# RAM_EMMC_Power.net
KiCad netlist of a schematic drawn in Altium Designer
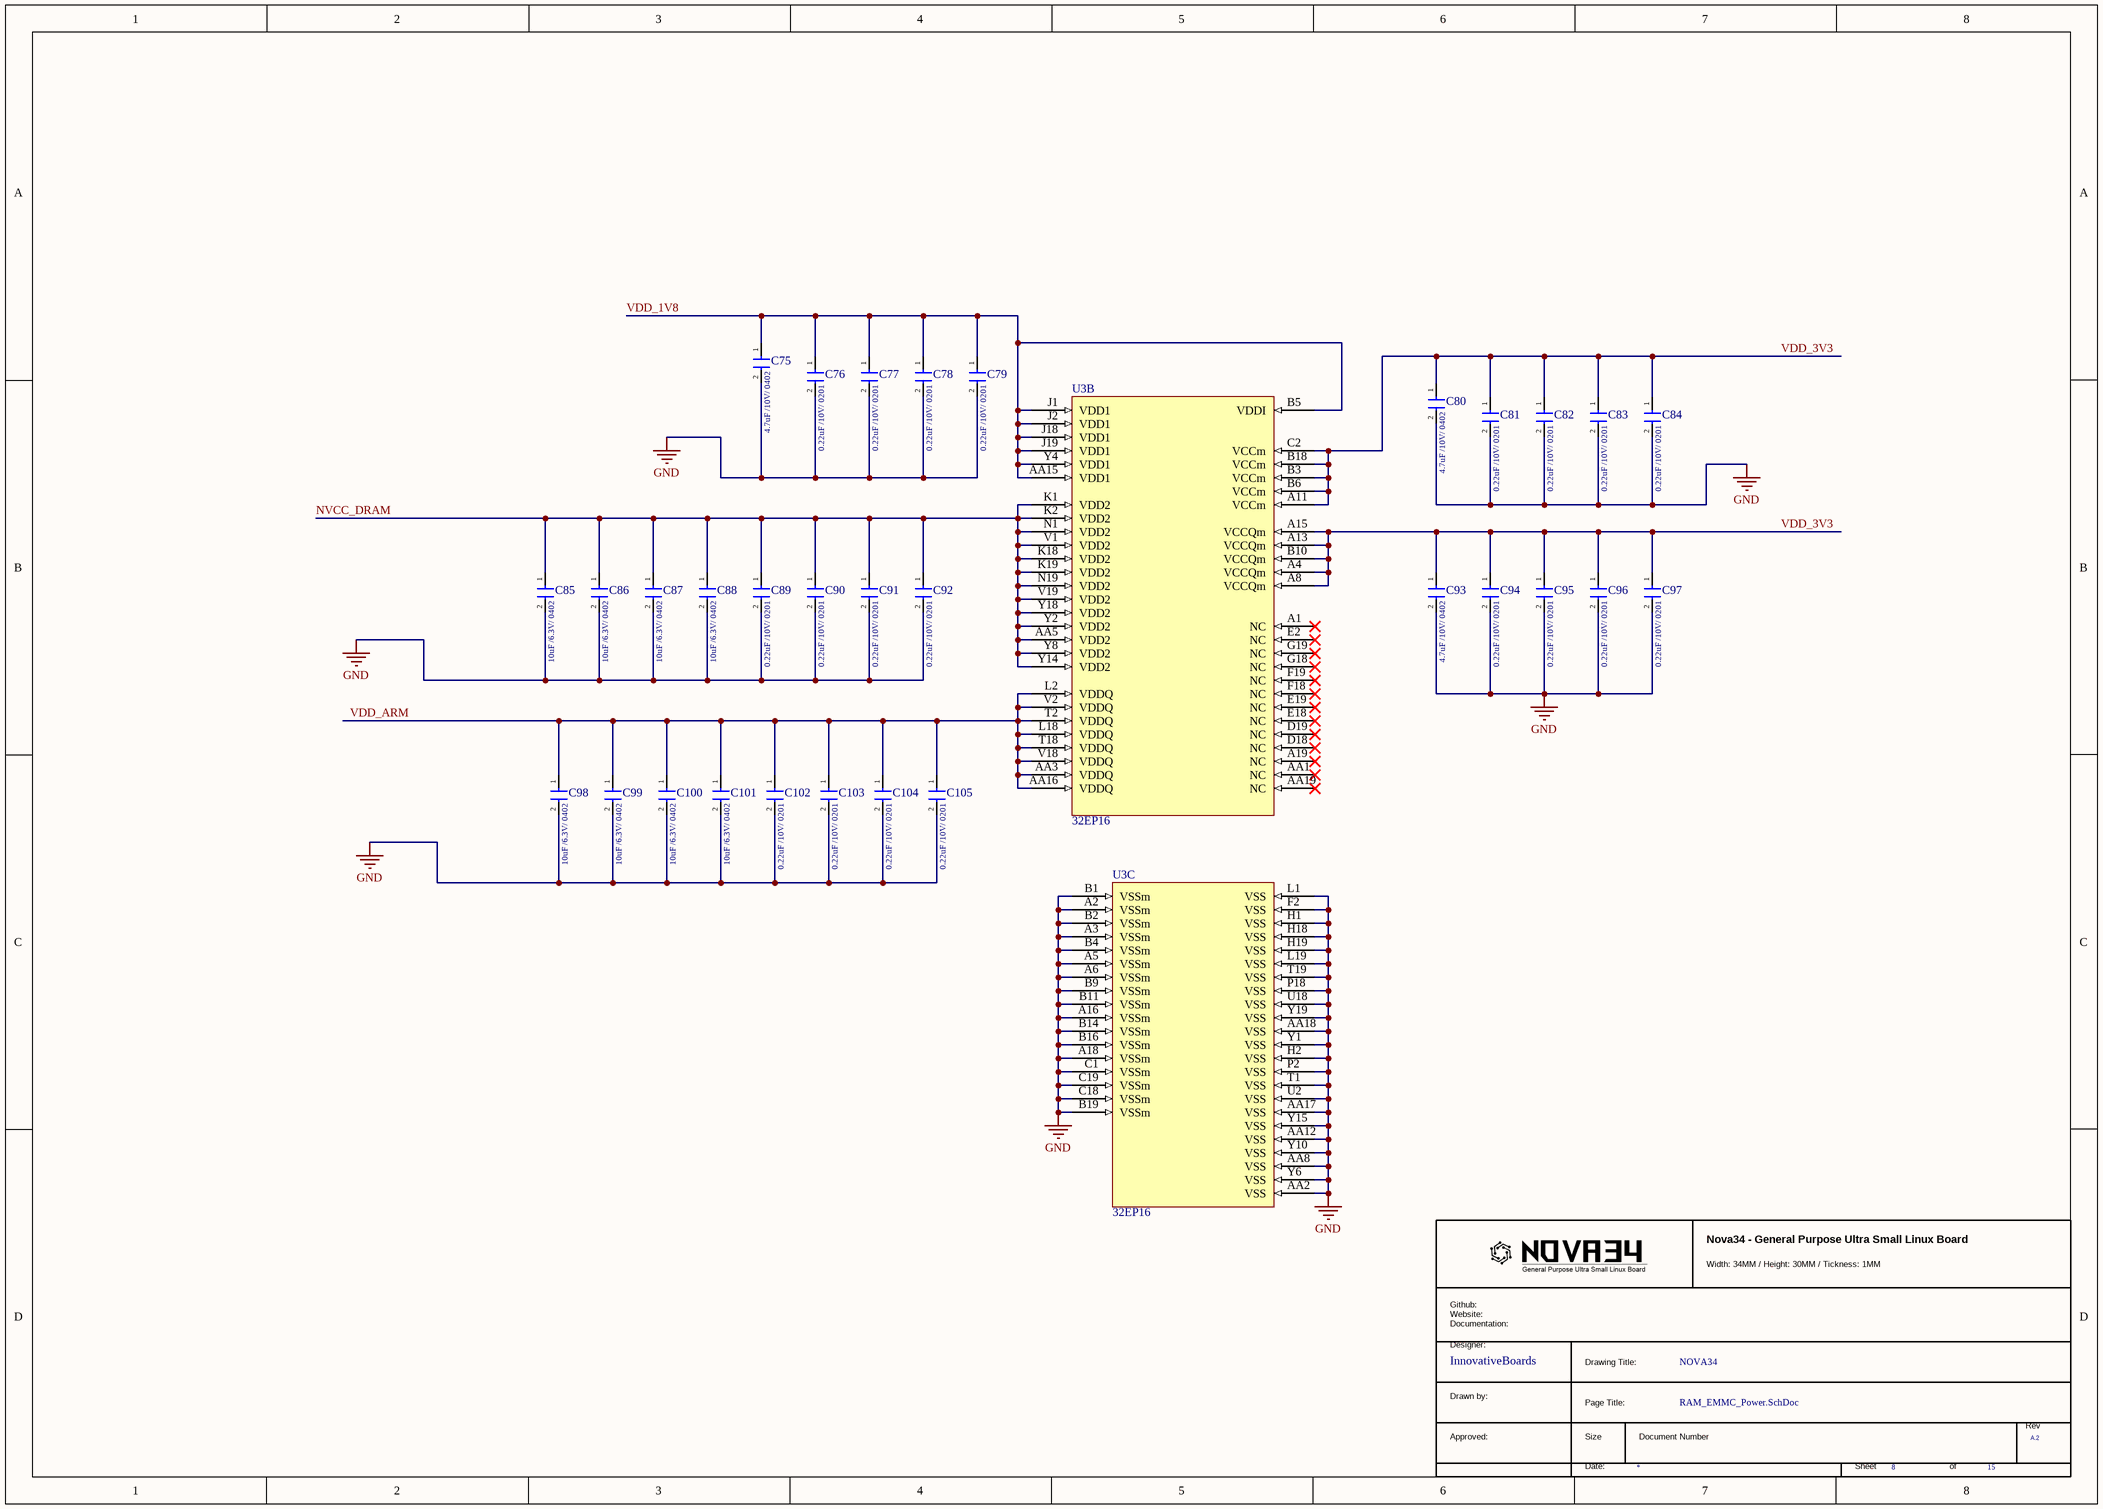
[diagram p0: RAM_EMMC_Power.SchDoc]

(export (version "E")
  (design (tool "Eeschema 10.0.6"))
  (components
    (comp (ref "C75")
      (value "4.7uF /10V/ 0402")
      (footprint "CAPC1005X70N")
      (description "Multilayer Ceramic Capacitors MLCC - SMD/SMT 0402 X6S 4.7 F 20 10VDC AEC-Q200")
      (fields
        (field (name "MANUFACTURER_PART_NUMBER") "GRT155C81A475ME13J")
        (field (name "MOUSER PART NUMBER") "81-GRT155C81A475ME3J")
      )
      (libsource (lib "Nova_SCHLIB") (part "GRT155C81A475ME13J"))
    )
    (comp (ref "C76")
      (value "0.22uF /10V/ 0201")
      (footprint "GRM033D70J224ME01D")
      (description "Multilayer Ceramic Capacitors MLCC - SMD/SMT 0201 10VDC 0.22 F 10 X6S")
      (fields
        (field (name "MANUFACTURER_PART_NUMBER") "GRM033C81A224KE01J")
        (field (name "MOUSER PART NUMBER") "81-GRM033C81A224KE1J")
      )
      (libsource (lib "Nova_SCHLIB") (part "GRM033C81A224KE01J"))
    )
    (comp (ref "C77")
      (value "0.22uF /10V/ 0201")
      (footprint "GRM033D70J224ME01D")
      (description "Multilayer Ceramic Capacitors MLCC - SMD/SMT 0201 10VDC 0.22 F 10 X6S")
      (fields
        (field (name "MANUFACTURER_PART_NUMBER") "GRM033C81A224KE01J")
        (field (name "MOUSER PART NUMBER") "81-GRM033C81A224KE1J")
      )
      (libsource (lib "Nova_SCHLIB") (part "GRM033C81A224KE01J"))
    )
    (comp (ref "C78")
      (value "0.22uF /10V/ 0201")
      (footprint "GRM033D70J224ME01D")
      (description "Multilayer Ceramic Capacitors MLCC - SMD/SMT 0201 10VDC 0.22 F 10 X6S")
      (fields
        (field (name "MANUFACTURER_PART_NUMBER") "GRM033C81A224KE01J")
        (field (name "MOUSER PART NUMBER") "81-GRM033C81A224KE1J")
      )
      (libsource (lib "Nova_SCHLIB") (part "GRM033C81A224KE01J"))
    )
    (comp (ref "C79")
      (value "0.22uF /10V/ 0201")
      (footprint "GRM033D70J224ME01D")
      (description "Multilayer Ceramic Capacitors MLCC - SMD/SMT 0201 10VDC 0.22 F 10 X6S")
      (fields
        (field (name "MANUFACTURER_PART_NUMBER") "GRM033C81A224KE01J")
        (field (name "MOUSER PART NUMBER") "81-GRM033C81A224KE1J")
      )
      (libsource (lib "Nova_SCHLIB") (part "GRM033C81A224KE01J"))
    )
    (comp (ref "C80")
      (value "4.7uF /10V/ 0402")
      (footprint "CAPC1005X70N")
      (description "Multilayer Ceramic Capacitors MLCC - SMD/SMT 0402 X6S 4.7 F 20 10VDC AEC-Q200")
      (fields
        (field (name "MANUFACTURER_PART_NUMBER") "GRT155C81A475ME13J")
        (field (name "MOUSER PART NUMBER") "81-GRT155C81A475ME3J")
      )
      (libsource (lib "Nova_SCHLIB") (part "GRT155C81A475ME13J"))
    )
    (comp (ref "C81")
      (value "0.22uF /10V/ 0201")
      (footprint "GRM033D70J224ME01D")
      (description "Multilayer Ceramic Capacitors MLCC - SMD/SMT 0201 10VDC 0.22 F 10 X6S")
      (fields
        (field (name "MANUFACTURER_PART_NUMBER") "GRM033C81A224KE01J")
        (field (name "MOUSER PART NUMBER") "81-GRM033C81A224KE1J")
      )
      (libsource (lib "Nova_SCHLIB") (part "GRM033C81A224KE01J"))
    )
    (comp (ref "C82")
      (value "0.22uF /10V/ 0201")
      (footprint "GRM033D70J224ME01D")
      (description "Multilayer Ceramic Capacitors MLCC - SMD/SMT 0201 10VDC 0.22 F 10 X6S")
      (fields
        (field (name "MANUFACTURER_PART_NUMBER") "GRM033C81A224KE01J")
        (field (name "MOUSER PART NUMBER") "81-GRM033C81A224KE1J")
      )
      (libsource (lib "Nova_SCHLIB") (part "GRM033C81A224KE01J"))
    )
    (comp (ref "C83")
      (value "0.22uF /10V/ 0201")
      (footprint "GRM033D70J224ME01D")
      (description "Multilayer Ceramic Capacitors MLCC - SMD/SMT 0201 10VDC 0.22 F 10 X6S")
      (fields
        (field (name "MANUFACTURER_PART_NUMBER") "GRM033C81A224KE01J")
        (field (name "MOUSER PART NUMBER") "81-GRM033C81A224KE1J")
      )
      (libsource (lib "Nova_SCHLIB") (part "GRM033C81A224KE01J"))
    )
    (comp (ref "C84")
      (value "0.22uF /10V/ 0201")
      (footprint "GRM033D70J224ME01D")
      (description "Multilayer Ceramic Capacitors MLCC - SMD/SMT 0201 10VDC 0.22 F 10 X6S")
      (fields
        (field (name "MANUFACTURER_PART_NUMBER") "GRM033C81A224KE01J")
        (field (name "MOUSER PART NUMBER") "81-GRM033C81A224KE1J")
      )
      (libsource (lib "Nova_SCHLIB") (part "GRM033C81A224KE01J"))
    )
    (comp (ref "C85")
      (value "10uF /6.3V/ 0402")
      (footprint "CAPC1005X65N")
      (description "Multilayer Ceramic Capacitors MLCC - SMD/SMT 10 uF 6.3 VDC 20% 0402 X5R")
      (fields
        (field (name "MANUFACTURER_PART_NUMBER") "GRM155R60J106ME15D")
        (field (name "MOUSER PART NUMBER") "81-GRM155R60J106ME5D")
      )
      (libsource (lib "Nova_SCHLIB") (part "GRM155R60J106ME15D"))
    )
    (comp (ref "C86")
      (value "10uF /6.3V/ 0402")
      (footprint "CAPC1005X65N")
      (description "Multilayer Ceramic Capacitors MLCC - SMD/SMT 10 uF 6.3 VDC 20% 0402 X5R")
      (fields
        (field (name "MANUFACTURER_PART_NUMBER") "GRM155R60J106ME15D")
        (field (name "MOUSER PART NUMBER") "81-GRM155R60J106ME5D")
      )
      (libsource (lib "Nova_SCHLIB") (part "GRM155R60J106ME15D"))
    )
    (comp (ref "C87")
      (value "10uF /6.3V/ 0402")
      (footprint "CAPC1005X65N")
      (description "Multilayer Ceramic Capacitors MLCC - SMD/SMT 10 uF 6.3 VDC 20% 0402 X5R")
      (fields
        (field (name "MANUFACTURER_PART_NUMBER") "GRM155R60J106ME15D")
        (field (name "MOUSER PART NUMBER") "81-GRM155R60J106ME5D")
      )
      (libsource (lib "Nova_SCHLIB") (part "GRM155R60J106ME15D"))
    )
    (comp (ref "C88")
      (value "10uF /6.3V/ 0402")
      (footprint "CAPC1005X65N")
      (description "Multilayer Ceramic Capacitors MLCC - SMD/SMT 10 uF 6.3 VDC 20% 0402 X5R")
      (fields
        (field (name "MANUFACTURER_PART_NUMBER") "GRM155R60J106ME15D")
        (field (name "MOUSER PART NUMBER") "81-GRM155R60J106ME5D")
      )
      (libsource (lib "Nova_SCHLIB") (part "GRM155R60J106ME15D"))
    )
    (comp (ref "C89")
      (value "0.22uF /10V/ 0201")
      (footprint "GRM033D70J224ME01D")
      (description "Multilayer Ceramic Capacitors MLCC - SMD/SMT 0201 10VDC 0.22 F 10 X6S")
      (fields
        (field (name "MANUFACTURER_PART_NUMBER") "GRM033C81A224KE01J")
        (field (name "MOUSER PART NUMBER") "81-GRM033C81A224KE1J")
      )
      (libsource (lib "Nova_SCHLIB") (part "GRM033C81A224KE01J"))
    )
    (comp (ref "C90")
      (value "0.22uF /10V/ 0201")
      (footprint "GRM033D70J224ME01D")
      (description "Multilayer Ceramic Capacitors MLCC - SMD/SMT 0201 10VDC 0.22 F 10 X6S")
      (fields
        (field (name "MANUFACTURER_PART_NUMBER") "GRM033C81A224KE01J")
        (field (name "MOUSER PART NUMBER") "81-GRM033C81A224KE1J")
      )
      (libsource (lib "Nova_SCHLIB") (part "GRM033C81A224KE01J"))
    )
    (comp (ref "C91")
      (value "0.22uF /10V/ 0201")
      (footprint "GRM033D70J224ME01D")
      (description "Multilayer Ceramic Capacitors MLCC - SMD/SMT 0201 10VDC 0.22 F 10 X6S")
      (fields
        (field (name "MANUFACTURER_PART_NUMBER") "GRM033C81A224KE01J")
        (field (name "MOUSER PART NUMBER") "81-GRM033C81A224KE1J")
      )
      (libsource (lib "Nova_SCHLIB") (part "GRM033C81A224KE01J"))
    )
    (comp (ref "C92")
      (value "0.22uF /10V/ 0201")
      (footprint "GRM033D70J224ME01D")
      (description "Multilayer Ceramic Capacitors MLCC - SMD/SMT 0201 10VDC 0.22 F 10 X6S")
      (fields
        (field (name "MANUFACTURER_PART_NUMBER") "GRM033C81A224KE01J")
        (field (name "MOUSER PART NUMBER") "81-GRM033C81A224KE1J")
      )
      (libsource (lib "Nova_SCHLIB") (part "GRM033C81A224KE01J"))
    )
    (comp (ref "C93")
      (value "4.7uF /10V/ 0402")
      (footprint "CAPC1005X70N")
      (description "Multilayer Ceramic Capacitors MLCC - SMD/SMT 0402 X6S 4.7 F 20 10VDC AEC-Q200")
      (fields
        (field (name "MANUFACTURER_PART_NUMBER") "GRT155C81A475ME13J")
        (field (name "MOUSER PART NUMBER") "81-GRT155C81A475ME3J")
      )
      (libsource (lib "Nova_SCHLIB") (part "GRT155C81A475ME13J"))
    )
    (comp (ref "C94")
      (value "0.22uF /10V/ 0201")
      (footprint "GRM033D70J224ME01D")
      (description "Multilayer Ceramic Capacitors MLCC - SMD/SMT 0201 10VDC 0.22 F 10 X6S")
      (fields
        (field (name "MANUFACTURER_PART_NUMBER") "GRM033C81A224KE01J")
        (field (name "MOUSER PART NUMBER") "81-GRM033C81A224KE1J")
      )
      (libsource (lib "Nova_SCHLIB") (part "GRM033C81A224KE01J"))
    )
    (comp (ref "C95")
      (value "0.22uF /10V/ 0201")
      (footprint "GRM033D70J224ME01D")
      (description "Multilayer Ceramic Capacitors MLCC - SMD/SMT 0201 10VDC 0.22 F 10 X6S")
      (fields
        (field (name "MANUFACTURER_PART_NUMBER") "GRM033C81A224KE01J")
        (field (name "MOUSER PART NUMBER") "81-GRM033C81A224KE1J")
      )
      (libsource (lib "Nova_SCHLIB") (part "GRM033C81A224KE01J"))
    )
    (comp (ref "C96")
      (value "0.22uF /10V/ 0201")
      (footprint "GRM033D70J224ME01D")
      (description "Multilayer Ceramic Capacitors MLCC - SMD/SMT 0201 10VDC 0.22 F 10 X6S")
      (fields
        (field (name "MANUFACTURER_PART_NUMBER") "GRM033C81A224KE01J")
        (field (name "MOUSER PART NUMBER") "81-GRM033C81A224KE1J")
      )
      (libsource (lib "Nova_SCHLIB") (part "GRM033C81A224KE01J"))
    )
    (comp (ref "C97")
      (value "0.22uF /10V/ 0201")
      (footprint "GRM033D70J224ME01D")
      (description "Multilayer Ceramic Capacitors MLCC - SMD/SMT 0201 10VDC 0.22 F 10 X6S")
      (fields
        (field (name "MANUFACTURER_PART_NUMBER") "GRM033C81A224KE01J")
        (field (name "MOUSER PART NUMBER") "81-GRM033C81A224KE1J")
      )
      (libsource (lib "Nova_SCHLIB") (part "GRM033C81A224KE01J"))
    )
    (comp (ref "C98")
      (value "10uF /6.3V/ 0402")
      (footprint "CAPC1005X65N")
      (description "Multilayer Ceramic Capacitors MLCC - SMD/SMT 10 uF 6.3 VDC 20% 0402 X5R")
      (fields
        (field (name "MANUFACTURER_PART_NUMBER") "GRM155R60J106ME15D")
        (field (name "MOUSER PART NUMBER") "81-GRM155R60J106ME5D")
      )
      (libsource (lib "Nova_SCHLIB") (part "GRM155R60J106ME15D"))
    )
    (comp (ref "C99")
      (value "10uF /6.3V/ 0402")
      (footprint "CAPC1005X65N")
      (description "Multilayer Ceramic Capacitors MLCC - SMD/SMT 10 uF 6.3 VDC 20% 0402 X5R")
      (fields
        (field (name "MANUFACTURER_PART_NUMBER") "GRM155R60J106ME15D")
        (field (name "MOUSER PART NUMBER") "81-GRM155R60J106ME5D")
      )
      (libsource (lib "Nova_SCHLIB") (part "GRM155R60J106ME15D"))
    )
    (comp (ref "C100")
      (value "10uF /6.3V/ 0402")
      (footprint "CAPC1005X65N")
      (description "Multilayer Ceramic Capacitors MLCC - SMD/SMT 10 uF 6.3 VDC 20% 0402 X5R")
      (fields
        (field (name "MANUFACTURER_PART_NUMBER") "GRM155R60J106ME15D")
        (field (name "MOUSER PART NUMBER") "81-GRM155R60J106ME5D")
      )
      (libsource (lib "Nova_SCHLIB") (part "GRM155R60J106ME15D"))
    )
    (comp (ref "C101")
      (value "10uF /6.3V/ 0402")
      (footprint "CAPC1005X65N")
      (description "Multilayer Ceramic Capacitors MLCC - SMD/SMT 10 uF 6.3 VDC 20% 0402 X5R")
      (fields
        (field (name "MANUFACTURER_PART_NUMBER") "GRM155R60J106ME15D")
        (field (name "MOUSER PART NUMBER") "81-GRM155R60J106ME5D")
      )
      (libsource (lib "Nova_SCHLIB") (part "GRM155R60J106ME15D"))
    )
    (comp (ref "C102")
      (value "0.22uF /10V/ 0201")
      (footprint "GRM033D70J224ME01D")
      (description "Multilayer Ceramic Capacitors MLCC - SMD/SMT 0201 10VDC 0.22 F 10 X6S")
      (fields
        (field (name "MANUFACTURER_PART_NUMBER") "GRM033C81A224KE01J")
        (field (name "MOUSER PART NUMBER") "81-GRM033C81A224KE1J")
      )
      (libsource (lib "Nova_SCHLIB") (part "GRM033C81A224KE01J"))
    )
    (comp (ref "C103")
      (value "0.22uF /10V/ 0201")
      (footprint "GRM033D70J224ME01D")
      (description "Multilayer Ceramic Capacitors MLCC - SMD/SMT 0201 10VDC 0.22 F 10 X6S")
      (fields
        (field (name "MANUFACTURER_PART_NUMBER") "GRM033C81A224KE01J")
        (field (name "MOUSER PART NUMBER") "81-GRM033C81A224KE1J")
      )
      (libsource (lib "Nova_SCHLIB") (part "GRM033C81A224KE01J"))
    )
    (comp (ref "C104")
      (value "0.22uF /10V/ 0201")
      (footprint "GRM033D70J224ME01D")
      (description "Multilayer Ceramic Capacitors MLCC - SMD/SMT 0201 10VDC 0.22 F 10 X6S")
      (fields
        (field (name "MANUFACTURER_PART_NUMBER") "GRM033C81A224KE01J")
        (field (name "MOUSER PART NUMBER") "81-GRM033C81A224KE1J")
      )
      (libsource (lib "Nova_SCHLIB") (part "GRM033C81A224KE01J"))
    )
    (comp (ref "C105")
      (value "0.22uF /10V/ 0201")
      (footprint "GRM033D70J224ME01D")
      (description "Multilayer Ceramic Capacitors MLCC - SMD/SMT 0201 10VDC 0.22 F 10 X6S")
      (fields
        (field (name "MANUFACTURER_PART_NUMBER") "GRM033C81A224KE01J")
        (field (name "MOUSER PART NUMBER") "81-GRM033C81A224KE1J")
      )
      (libsource (lib "Nova_SCHLIB") (part "GRM033C81A224KE01J"))
    )
    (comp (ref "U3")
      (value "32EP16")
      (footprint "BGA144C40P19X21_800X950X80")
      (libsource (lib "Nova_SCHLIB") (part "32EP16"))
    )
  )
  (nets
    (net (code "1") (name "/NVCC_DRAM") (class "Default")
      (node (ref "C85") (pin "1") (pinfunction "1_1") (pintype "passive"))
      (node (ref "C86") (pin "1") (pinfunction "1_1") (pintype "passive"))
      (node (ref "C87") (pin "1") (pinfunction "1_1") (pintype "passive"))
      (node (ref "C88") (pin "1") (pinfunction "1_1") (pintype "passive"))
      (node (ref "C89") (pin "1") (pinfunction "1_1") (pintype "passive"))
      (node (ref "C90") (pin "1") (pinfunction "1_1") (pintype "passive"))
      (node (ref "C91") (pin "1") (pinfunction "1_1") (pintype "passive"))
      (node (ref "C92") (pin "1") (pinfunction "1_1") (pintype "passive"))
      (node (ref "U3") (pin "AA5") (pinfunction "VDD2_AA5") (pintype "input"))
      (node (ref "U3") (pin "K1") (pinfunction "VDD2_K1") (pintype "input"))
      (node (ref "U3") (pin "K18") (pinfunction "VDD2_K18") (pintype "input"))
      (node (ref "U3") (pin "K19") (pinfunction "VDD2_K19") (pintype "input"))
      (node (ref "U3") (pin "K2") (pinfunction "VDD2_K2") (pintype "input"))
      (node (ref "U3") (pin "N1") (pinfunction "VDD2_N1") (pintype "input"))
      (node (ref "U3") (pin "N19") (pinfunction "VDD2_N19") (pintype "input"))
      (node (ref "U3") (pin "V1") (pinfunction "VDD2_V1") (pintype "input"))
      (node (ref "U3") (pin "V19") (pinfunction "VDD2_V19") (pintype "input"))
      (node (ref "U3") (pin "Y14") (pinfunction "VDD2_Y14") (pintype "input"))
      (node (ref "U3") (pin "Y18") (pinfunction "VDD2_Y18") (pintype "input"))
      (node (ref "U3") (pin "Y2") (pinfunction "VDD2_Y2") (pintype "input"))
      (node (ref "U3") (pin "Y8") (pinfunction "VDD2_Y8") (pintype "input"))
    )
    (net (code "2") (name "/VDD_1V8") (class "Default")
      (node (ref "C75") (pin "1") (pinfunction "1_1") (pintype "passive"))
      (node (ref "C76") (pin "1") (pinfunction "1_1") (pintype "passive"))
      (node (ref "C77") (pin "1") (pinfunction "1_1") (pintype "passive"))
      (node (ref "C78") (pin "1") (pinfunction "1_1") (pintype "passive"))
      (node (ref "C79") (pin "1") (pinfunction "1_1") (pintype "passive"))
      (node (ref "U3") (pin "AA15") (pinfunction "VDD1_AA15") (pintype "input"))
      (node (ref "U3") (pin "B5") (pinfunction "VDDI_B5") (pintype "input"))
      (node (ref "U3") (pin "J1") (pinfunction "VDD1_J1") (pintype "input"))
      (node (ref "U3") (pin "J18") (pinfunction "VDD1_J18") (pintype "input"))
      (node (ref "U3") (pin "J19") (pinfunction "VDD1_J19") (pintype "input"))
      (node (ref "U3") (pin "J2") (pinfunction "VDD1_J2") (pintype "input"))
      (node (ref "U3") (pin "Y4") (pinfunction "VDD1_Y4") (pintype "input"))
    )
    (net (code "3") (name "/VDD_3V3") (class "Default")
      (node (ref "C80") (pin "1") (pinfunction "1_1") (pintype "passive"))
      (node (ref "C81") (pin "1") (pinfunction "1_1") (pintype "passive"))
      (node (ref "C82") (pin "1") (pinfunction "1_1") (pintype "passive"))
      (node (ref "C83") (pin "1") (pinfunction "1_1") (pintype "passive"))
      (node (ref "C84") (pin "1") (pinfunction "1_1") (pintype "passive"))
      (node (ref "C93") (pin "1") (pinfunction "1_1") (pintype "passive"))
      (node (ref "C94") (pin "1") (pinfunction "1_1") (pintype "passive"))
      (node (ref "C95") (pin "1") (pinfunction "1_1") (pintype "passive"))
      (node (ref "C96") (pin "1") (pinfunction "1_1") (pintype "passive"))
      (node (ref "C97") (pin "1") (pinfunction "1_1") (pintype "passive"))
      (node (ref "U3") (pin "A11") (pinfunction "VCCm_A11") (pintype "input"))
      (node (ref "U3") (pin "A13") (pinfunction "VCCQm_A13") (pintype "input"))
      (node (ref "U3") (pin "A15") (pinfunction "VCCQm_A15") (pintype "input"))
      (node (ref "U3") (pin "A4") (pinfunction "VCCQm_A4") (pintype "input"))
      (node (ref "U3") (pin "A8") (pinfunction "VCCQm_A8") (pintype "input"))
      (node (ref "U3") (pin "B10") (pinfunction "VCCQm_B10") (pintype "input"))
      (node (ref "U3") (pin "B18") (pinfunction "VCCm_B18") (pintype "input"))
      (node (ref "U3") (pin "B3") (pinfunction "VCCm_B3") (pintype "input"))
      (node (ref "U3") (pin "B6") (pinfunction "VCCm_B6") (pintype "input"))
      (node (ref "U3") (pin "C2") (pinfunction "VCCm_C2") (pintype "input"))
    )
    (net (code "4") (name "/VDD_ARM") (class "Default")
      (node (ref "C100") (pin "1") (pinfunction "1_1") (pintype "passive"))
      (node (ref "C101") (pin "1") (pinfunction "1_1") (pintype "passive"))
      (node (ref "C102") (pin "1") (pinfunction "1_1") (pintype "passive"))
      (node (ref "C103") (pin "1") (pinfunction "1_1") (pintype "passive"))
      (node (ref "C104") (pin "1") (pinfunction "1_1") (pintype "passive"))
      (node (ref "C105") (pin "1") (pinfunction "1_1") (pintype "passive"))
      (node (ref "C98") (pin "1") (pinfunction "1_1") (pintype "passive"))
      (node (ref "C99") (pin "1") (pinfunction "1_1") (pintype "passive"))
      (node (ref "U3") (pin "AA16") (pinfunction "VDDQ_AA16") (pintype "input"))
      (node (ref "U3") (pin "AA3") (pinfunction "VDDQ_AA3") (pintype "input"))
      (node (ref "U3") (pin "L18") (pinfunction "VDDQ_L18") (pintype "input"))
      (node (ref "U3") (pin "L2") (pinfunction "VDDQ_L2") (pintype "input"))
      (node (ref "U3") (pin "T18") (pinfunction "VDDQ_T18") (pintype "input"))
      (node (ref "U3") (pin "T2") (pinfunction "VDDQ_T2") (pintype "input"))
      (node (ref "U3") (pin "V18") (pinfunction "VDDQ_V18") (pintype "input"))
      (node (ref "U3") (pin "V2") (pinfunction "VDDQ_V2") (pintype "input"))
    )
    (net (code "5") (name "GND") (class "Default")
      (node (ref "C100") (pin "2") (pinfunction "2_2") (pintype "passive"))
      (node (ref "C101") (pin "2") (pinfunction "2_2") (pintype "passive"))
      (node (ref "C102") (pin "2") (pinfunction "2_2") (pintype "passive"))
      (node (ref "C103") (pin "2") (pinfunction "2_2") (pintype "passive"))
      (node (ref "C104") (pin "2") (pinfunction "2_2") (pintype "passive"))
      (node (ref "C105") (pin "2") (pinfunction "2_2") (pintype "passive"))
      (node (ref "C75") (pin "2") (pinfunction "2_2") (pintype "passive"))
      (node (ref "C76") (pin "2") (pinfunction "2_2") (pintype "passive"))
      (node (ref "C77") (pin "2") (pinfunction "2_2") (pintype "passive"))
      (node (ref "C78") (pin "2") (pinfunction "2_2") (pintype "passive"))
      (node (ref "C79") (pin "2") (pinfunction "2_2") (pintype "passive"))
      (node (ref "C80") (pin "2") (pinfunction "2_2") (pintype "passive"))
      (node (ref "C81") (pin "2") (pinfunction "2_2") (pintype "passive"))
      (node (ref "C82") (pin "2") (pinfunction "2_2") (pintype "passive"))
      (node (ref "C83") (pin "2") (pinfunction "2_2") (pintype "passive"))
      (node (ref "C84") (pin "2") (pinfunction "2_2") (pintype "passive"))
      (node (ref "C85") (pin "2") (pinfunction "2_2") (pintype "passive"))
      (node (ref "C86") (pin "2") (pinfunction "2_2") (pintype "passive"))
      (node (ref "C87") (pin "2") (pinfunction "2_2") (pintype "passive"))
      (node (ref "C88") (pin "2") (pinfunction "2_2") (pintype "passive"))
      (node (ref "C89") (pin "2") (pinfunction "2_2") (pintype "passive"))
      (node (ref "C90") (pin "2") (pinfunction "2_2") (pintype "passive"))
      (node (ref "C91") (pin "2") (pinfunction "2_2") (pintype "passive"))
      (node (ref "C92") (pin "2") (pinfunction "2_2") (pintype "passive"))
      (node (ref "C93") (pin "2") (pinfunction "2_2") (pintype "passive"))
      (node (ref "C94") (pin "2") (pinfunction "2_2") (pintype "passive"))
      (node (ref "C95") (pin "2") (pinfunction "2_2") (pintype "passive"))
      (node (ref "C96") (pin "2") (pinfunction "2_2") (pintype "passive"))
      (node (ref "C97") (pin "2") (pinfunction "2_2") (pintype "passive"))
      (node (ref "C98") (pin "2") (pinfunction "2_2") (pintype "passive"))
      (node (ref "C99") (pin "2") (pinfunction "2_2") (pintype "passive"))
      (node (ref "U3") (pin "A16") (pinfunction "VSSm_A16") (pintype "input"))
      (node (ref "U3") (pin "A18") (pinfunction "VSSm_A18") (pintype "input"))
      (node (ref "U3") (pin "A2") (pinfunction "VSSm_A2") (pintype "input"))
      (node (ref "U3") (pin "A3") (pinfunction "VSSm_A3") (pintype "input"))
      (node (ref "U3") (pin "A5") (pinfunction "VSSm_A5") (pintype "input"))
      (node (ref "U3") (pin "A6") (pinfunction "VSSm_A6") (pintype "input"))
      (node (ref "U3") (pin "AA12") (pinfunction "VSS_AA12") (pintype "input"))
      (node (ref "U3") (pin "AA17") (pinfunction "VSS_AA17") (pintype "input"))
      (node (ref "U3") (pin "AA18") (pinfunction "VSS_AA18") (pintype "input"))
      (node (ref "U3") (pin "AA2") (pinfunction "VSS_AA2") (pintype "input"))
      (node (ref "U3") (pin "AA8") (pinfunction "VSS_AA8") (pintype "input"))
      (node (ref "U3") (pin "B1") (pinfunction "VSSm_B1") (pintype "input"))
      (node (ref "U3") (pin "B11") (pinfunction "VSSm_B11") (pintype "input"))
      (node (ref "U3") (pin "B14") (pinfunction "VSSm_B14") (pintype "input"))
      (node (ref "U3") (pin "B16") (pinfunction "VSSm_B16") (pintype "input"))
      (node (ref "U3") (pin "B19") (pinfunction "VSSm_B19") (pintype "input"))
      (node (ref "U3") (pin "B2") (pinfunction "VSSm_B2") (pintype "input"))
      (node (ref "U3") (pin "B4") (pinfunction "VSSm_B4") (pintype "input"))
      (node (ref "U3") (pin "B9") (pinfunction "VSSm_B9") (pintype "input"))
      (node (ref "U3") (pin "C1") (pinfunction "VSSm_C1") (pintype "input"))
      (node (ref "U3") (pin "C18") (pinfunction "VSSm_C18") (pintype "input"))
      (node (ref "U3") (pin "C19") (pinfunction "VSSm_C19") (pintype "input"))
      (node (ref "U3") (pin "F2") (pinfunction "VSS_F2") (pintype "input"))
      (node (ref "U3") (pin "H1") (pinfunction "VSS_H1") (pintype "input"))
      (node (ref "U3") (pin "H18") (pinfunction "VSS_H18") (pintype "input"))
      (node (ref "U3") (pin "H19") (pinfunction "VSS_H19") (pintype "input"))
      (node (ref "U3") (pin "H2") (pinfunction "VSS_H2") (pintype "input"))
      (node (ref "U3") (pin "L1") (pinfunction "VSS_L1") (pintype "input"))
      (node (ref "U3") (pin "L19") (pinfunction "VSS_L19") (pintype "input"))
      (node (ref "U3") (pin "P18") (pinfunction "VSS_P18") (pintype "input"))
      (node (ref "U3") (pin "P2") (pinfunction "VSS_P2") (pintype "input"))
      (node (ref "U3") (pin "T1") (pinfunction "VSS_T1") (pintype "input"))
      (node (ref "U3") (pin "T19") (pinfunction "VSS_T19") (pintype "input"))
      (node (ref "U3") (pin "U18") (pinfunction "VSS_U18") (pintype "input"))
      (node (ref "U3") (pin "U2") (pinfunction "VSS_U2") (pintype "input"))
      (node (ref "U3") (pin "Y1") (pinfunction "VSS_Y1") (pintype "input"))
      (node (ref "U3") (pin "Y10") (pinfunction "VSS_Y10") (pintype "input"))
      (node (ref "U3") (pin "Y15") (pinfunction "VSS_Y15") (pintype "input"))
      (node (ref "U3") (pin "Y19") (pinfunction "VSS_Y19") (pintype "input"))
      (node (ref "U3") (pin "Y6") (pinfunction "VSS_Y6") (pintype "input"))
    )
    (net (code "6") (name "unconnected-(U3B-NC-PadA1)") (class "Default")
      (node (ref "U3") (pin "A1") (pinfunction "NC_A1") (pintype "input+no_connect"))
    )
    (net (code "7") (name "unconnected-(U3B-NC-PadA19)") (class "Default")
      (node (ref "U3") (pin "A19") (pinfunction "NC_A19") (pintype "input+no_connect"))
    )
    (net (code "8") (name "unconnected-(U3B-NC-PadAA1)") (class "Default")
      (node (ref "U3") (pin "AA1") (pinfunction "NC_AA1") (pintype "input+no_connect"))
    )
    (net (code "9") (name "unconnected-(U3B-NC-PadAA19)") (class "Default")
      (node (ref "U3") (pin "AA19") (pinfunction "NC_AA19") (pintype "input+no_connect"))
    )
    (net (code "10") (name "unconnected-(U3B-NC-PadD18)") (class "Default")
      (node (ref "U3") (pin "D18") (pinfunction "NC_D18") (pintype "input+no_connect"))
    )
    (net (code "11") (name "unconnected-(U3B-NC-PadD19)") (class "Default")
      (node (ref "U3") (pin "D19") (pinfunction "NC_D19") (pintype "input+no_connect"))
    )
    (net (code "12") (name "unconnected-(U3B-NC-PadE2)") (class "Default")
      (node (ref "U3") (pin "E2") (pinfunction "NC_E2") (pintype "input+no_connect"))
    )
    (net (code "13") (name "unconnected-(U3B-NC-PadE18)") (class "Default")
      (node (ref "U3") (pin "E18") (pinfunction "NC_E18") (pintype "input+no_connect"))
    )
    (net (code "14") (name "unconnected-(U3B-NC-PadE19)") (class "Default")
      (node (ref "U3") (pin "E19") (pinfunction "NC_E19") (pintype "input+no_connect"))
    )
    (net (code "15") (name "unconnected-(U3B-NC-PadF18)") (class "Default")
      (node (ref "U3") (pin "F18") (pinfunction "NC_F18") (pintype "input+no_connect"))
    )
    (net (code "16") (name "unconnected-(U3B-NC-PadF19)") (class "Default")
      (node (ref "U3") (pin "F19") (pinfunction "NC_F19") (pintype "input+no_connect"))
    )
    (net (code "17") (name "unconnected-(U3B-NC-PadG18)") (class "Default")
      (node (ref "U3") (pin "G18") (pinfunction "NC_G18") (pintype "input+no_connect"))
    )
    (net (code "18") (name "unconnected-(U3B-NC-PadG19)") (class "Default")
      (node (ref "U3") (pin "G19") (pinfunction "NC_G19") (pintype "input+no_connect"))
    )
  )
)
